# H_bridge.net
KiCad netlist of a schematic drawn in Altium Designer
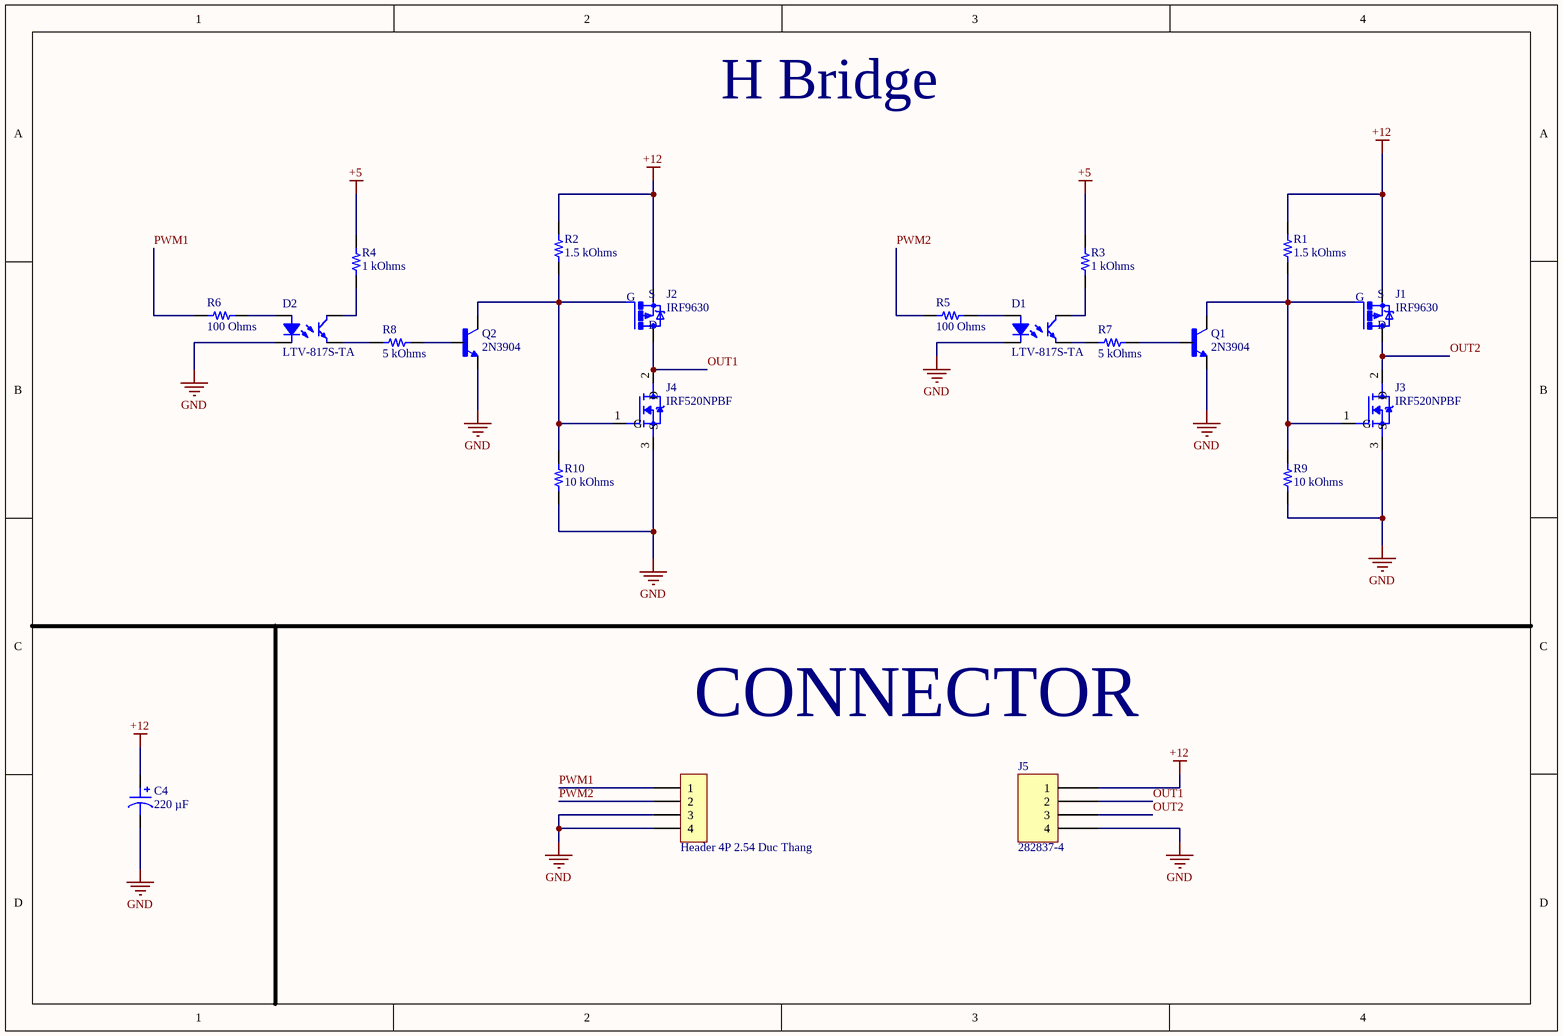
[diagram p0: H_bridge.SchDoc]

(export (version "E")
  (design (tool "Eeschema 10.0.6"))
  (components
    (comp (ref "C4")
      (value "220 µF")
      (footprint "CAP ALSMD POLY 8.3MM H10.0MM")
      (description "CAP ALUM POLY 220UF 20% 25V SMD")
      (fields (field (name "PART NUMBER") "PCR1E221MCL6GS") (field (name "MANUFACTURER") "Nichicon"))
      (libsource (lib "Celestial Altium Library - altium_library") (part "Polarised Capacitor"))
    )
    (comp (ref "D1")
      (value "LTV-817S-TA")
      (footprint "LITEON LTV-817")
      (description "OPTOISOLATR 5KV TRANSISTOR 4-SMD")
      (fields (field (name "MANUFACTURER") "Lite-On Inc."))
      (libsource (lib "Celestial Altium Library - altium_library") (part "Optoisolator"))
    )
    (comp (ref "D2")
      (value "LTV-817S-TA")
      (footprint "LITEON LTV-817")
      (description "OPTOISOLATR 5KV TRANSISTOR 4-SMD")
      (fields (field (name "MANUFACTURER") "Lite-On Inc."))
      (libsource (lib "Celestial Altium Library - altium_library") (part "Optoisolator"))
    )
    (comp (ref "H1")
      (value "Header 4P 2.54 Duc Thang")
      (footprint "XH2.54M-4")
      (description "Cắm")
      (libsource (lib "Header") (part "Header 4P 2.54 Duc Thang"))
    )
    (comp (ref "J1")
      (value "IRF9630")
      (footprint "TO220V")
      (fields (field (name "MF") "Vishay Siliconix"))
      (libsource (lib "IRF9630") (part "IRF9630"))
    )
    (comp (ref "J2")
      (value "IRF9630")
      (footprint "TO220V")
      (fields (field (name "MF") "Vishay Siliconix"))
      (libsource (lib "IRF9630") (part "IRF9630"))
    )
    (comp (ref "J3")
      (value "IRF520NPBF")
      (footprint "TO-220-3")
      (description "N-Channel 100V 9.7A _Tc_ 48W _Tc_ Through Hole TO-220AB")
      (fields (field (name "MF") "Infineon Technologies"))
      (libsource (lib "IRF520NPBF") (part "IRF520NPBF"))
    )
    (comp (ref "J4")
      (value "IRF520NPBF")
      (footprint "TO-220-3")
      (description "N-Channel 100V 9.7A _Tc_ 48W _Tc_ Through Hole TO-220AB")
      (fields (field (name "MF") "Infineon Technologies"))
      (libsource (lib "IRF520NPBF") (part "IRF520NPBF"))
    )
    (comp (ref "J5")
      (value "282837-4")
      (footprint "TE 282837-4")
      (description "TERM BLK 4P SIDE ENT 5.08MM PCB")
      (fields (field (name "MANUFACTURER") "TE Connectivity AMP Connectors") (field (name "VOLTAGE") "300 V"))
      (libsource (lib "Celestial Altium Library - altium_library") (part "4 Pin"))
    )
    (comp (ref "Q1")
      (value "2N3904")
      (footprint "TO92127P495H495-3")
      (description "TRANS NPN 40V 200MA TO92-3")
      (fields (field (name "MF") "Rectron"))
      (libsource (lib "2N3904") (part "2N3904"))
    )
    (comp (ref "Q2")
      (value "2N3904")
      (footprint "TO92127P495H495-3")
      (description "TRANS NPN 40V 200MA TO92-3")
      (fields (field (name "MF") "Rectron"))
      (libsource (lib "2N3904") (part "2N3904"))
    )
    (comp (ref "R1")
      (value "1.5 kOhms")
      (footprint "RES 0603_1608")
      (description "RES 1.5K OHM 0.1% 1/10W 0603")
      (fields (field (name "PART NUMBER") "RP0603BRD071K5L") (field (name "MANUFACTURER") "Yageo"))
      (libsource (lib "Celestial Altium Library - altium_library") (part "Resistor"))
    )
    (comp (ref "R2")
      (value "1.5 kOhms")
      (footprint "RES 0603_1608")
      (description "RES 1.5K OHM 0.1% 1/10W 0603")
      (fields (field (name "PART NUMBER") "RP0603BRD071K5L") (field (name "MANUFACTURER") "Yageo"))
      (libsource (lib "Celestial Altium Library - altium_library") (part "Resistor"))
    )
    (comp (ref "R3")
      (value "1 kOhms")
      (footprint "RES 0603_1608")
      (description "RES 1K OHM 0.1% 1/10W 0603")
      (fields (field (name "PART NUMBER") "RP0603BRD071KL") (field (name "MANUFACTURER") "Yageo"))
      (libsource (lib "Celestial Altium Library - altium_library") (part "Resistor"))
    )
    (comp (ref "R4")
      (value "1 kOhms")
      (footprint "RES 0603_1608")
      (description "RES 1K OHM 0.1% 1/10W 0603")
      (fields (field (name "PART NUMBER") "RP0603BRD071KL") (field (name "MANUFACTURER") "Yageo"))
      (libsource (lib "Celestial Altium Library - altium_library") (part "Resistor"))
    )
    (comp (ref "R5")
      (value "100 Ohms")
      (footprint "RES 0603_1608")
      (description "RES SMD 100 OHM 0.1% 1/10W 0603")
      (fields
        (field (name "PART NUMBER") "MCT06030D1000BP100")
        (field (name "MANUFACTURER") "Vishay Beyschlag")
      )
      (libsource (lib "Celestial Altium Library - altium_library") (part "Resistor"))
    )
    (comp (ref "R6")
      (value "100 Ohms")
      (footprint "RES 0603_1608")
      (description "RES SMD 100 OHM 0.1% 1/10W 0603")
      (fields
        (field (name "PART NUMBER") "MCT06030D1000BP100")
        (field (name "MANUFACTURER") "Vishay Beyschlag")
      )
      (libsource (lib "Celestial Altium Library - altium_library") (part "Resistor"))
    )
    (comp (ref "R7")
      (value "5 kOhms")
      (footprint "RES 0603_1608")
      (description "RES SMD 5K OHM 0.1% 0.15W 0603")
      (fields
        (field (name "PART NUMBER") "PNM0603E5001BST5")
        (field (name "MANUFACTURER") "Vishay Thin Film")
      )
      (libsource (lib "Celestial Altium Library - altium_library") (part "Resistor"))
    )
    (comp (ref "R8")
      (value "5 kOhms")
      (footprint "RES 0603_1608")
      (description "RES SMD 5K OHM 0.1% 0.15W 0603")
      (fields
        (field (name "PART NUMBER") "PNM0603E5001BST5")
        (field (name "MANUFACTURER") "Vishay Thin Film")
      )
      (libsource (lib "Celestial Altium Library - altium_library") (part "Resistor"))
    )
    (comp (ref "R9")
      (value "10 kOhms")
      (footprint "RES 0603_1608")
      (description "RES SMD 10K OHM 1/10W 0.1% 0603")
      (fields (field (name "PART NUMBER") "CRT0603-BY-1002EAS") (field (name "MANUFACTURER") "Bourns Inc."))
      (libsource (lib "Celestial Altium Library - altium_library") (part "Resistor"))
    )
    (comp (ref "R10")
      (value "10 kOhms")
      (footprint "RES 0603_1608")
      (description "RES SMD 10K OHM 1/10W 0.1% 0603")
      (fields (field (name "PART NUMBER") "CRT0603-BY-1002EAS") (field (name "MANUFACTURER") "Bourns Inc."))
      (libsource (lib "Celestial Altium Library - altium_library") (part "Resistor"))
    )
  )
  (nets
    (net (code "1") (name "+5") (class "Default")
      (node (ref "R3") (pin "2") (pinfunction "2_2") (pintype "passive"))
      (node (ref "R4") (pin "2") (pinfunction "2_2") (pintype "passive"))
    )
    (net (code "2") (name "+12") (class "Default")
      (node (ref "C4") (pin "1") (pinfunction "1_1") (pintype "passive"))
      (node (ref "J1") (pin "3") (pinfunction "S_3") (pintype "passive"))
      (node (ref "J2") (pin "3") (pinfunction "S_3") (pintype "passive"))
      (node (ref "J5") (pin "1") (pinfunction "1_1") (pintype "passive"))
      (node (ref "R1") (pin "2") (pinfunction "2_2") (pintype "passive"))
      (node (ref "R2") (pin "2") (pinfunction "2_2") (pintype "passive"))
    )
    (net (code "3") (name "/OUT1") (class "Default")
      (node (ref "J2") (pin "2") (pinfunction "D_2") (pintype "passive"))
      (node (ref "J4") (pin "2") (pinfunction "D_2") (pintype "passive"))
      (node (ref "J5") (pin "2") (pinfunction "2_2") (pintype "passive"))
    )
    (net (code "4") (name "/OUT2") (class "Default")
      (node (ref "J1") (pin "2") (pinfunction "D_2") (pintype "passive"))
      (node (ref "J3") (pin "2") (pinfunction "D_2") (pintype "passive"))
      (node (ref "J5") (pin "3") (pinfunction "3_3") (pintype "passive"))
    )
    (net (code "5") (name "/PWM1") (class "Default")
      (node (ref "H1") (pin "1") (pinfunction "1_1") (pintype "passive"))
      (node (ref "R6") (pin "1") (pinfunction "1_1") (pintype "passive"))
    )
    (net (code "6") (name "/PWM2") (class "Default")
      (node (ref "H1") (pin "2") (pinfunction "2_2") (pintype "passive"))
      (node (ref "R5") (pin "1") (pinfunction "1_1") (pintype "passive"))
    )
    (net (code "7") (name "GND") (class "Default")
      (node (ref "C4") (pin "2") (pinfunction "2_2") (pintype "passive"))
      (node (ref "D1") (pin "2") (pinfunction "2_2") (pintype "passive"))
      (node (ref "D2") (pin "2") (pinfunction "2_2") (pintype "passive"))
      (node (ref "H1") (pin "3") (pinfunction "3_3") (pintype "passive"))
      (node (ref "H1") (pin "4") (pinfunction "4_4") (pintype "passive"))
      (node (ref "J3") (pin "3") (pinfunction "S_3") (pintype "passive"))
      (node (ref "J4") (pin "3") (pinfunction "S_3") (pintype "passive"))
      (node (ref "J5") (pin "4") (pinfunction "4_4") (pintype "passive"))
      (node (ref "Q1") (pin "1") (pinfunction "E_1") (pintype "passive"))
      (node (ref "Q2") (pin "1") (pinfunction "E_1") (pintype "passive"))
      (node (ref "R10") (pin "1") (pinfunction "1_1") (pintype "passive"))
      (node (ref "R9") (pin "1") (pinfunction "1_1") (pintype "passive"))
    )
    (net (code "8") (name "Net-(D1-Pad1)") (class "Default")
      (node (ref "D1") (pin "1") (pinfunction "1_1") (pintype "passive"))
      (node (ref "R5") (pin "2") (pinfunction "2_2") (pintype "passive"))
    )
    (net (code "9") (name "Net-(D1-Pad3)") (class "Default")
      (node (ref "D1") (pin "3") (pinfunction "3_3") (pintype "passive"))
      (node (ref "R7") (pin "1") (pinfunction "1_1") (pintype "passive"))
    )
    (net (code "10") (name "Net-(D1-Pad4)") (class "Default")
      (node (ref "D1") (pin "4") (pinfunction "4_4") (pintype "passive"))
      (node (ref "R3") (pin "1") (pinfunction "1_1") (pintype "passive"))
    )
    (net (code "11") (name "Net-(D2-Pad1)") (class "Default")
      (node (ref "D2") (pin "1") (pinfunction "1_1") (pintype "passive"))
      (node (ref "R6") (pin "2") (pinfunction "2_2") (pintype "passive"))
    )
    (net (code "12") (name "Net-(D2-Pad3)") (class "Default")
      (node (ref "D2") (pin "3") (pinfunction "3_3") (pintype "passive"))
      (node (ref "R8") (pin "1") (pinfunction "1_1") (pintype "passive"))
    )
    (net (code "13") (name "Net-(D2-Pad4)") (class "Default")
      (node (ref "D2") (pin "4") (pinfunction "4_4") (pintype "passive"))
      (node (ref "R4") (pin "1") (pinfunction "1_1") (pintype "passive"))
    )
    (net (code "14") (name "Net-(J1-G)") (class "Default")
      (node (ref "J1") (pin "1") (pinfunction "G_1") (pintype "passive"))
      (node (ref "J3") (pin "1") (pinfunction "G_1") (pintype "passive"))
      (node (ref "Q1") (pin "3") (pinfunction "C_3") (pintype "passive"))
      (node (ref "R1") (pin "1") (pinfunction "1_1") (pintype "passive"))
      (node (ref "R9") (pin "2") (pinfunction "2_2") (pintype "passive"))
    )
    (net (code "15") (name "Net-(J2-G)") (class "Default")
      (node (ref "J2") (pin "1") (pinfunction "G_1") (pintype "passive"))
      (node (ref "J4") (pin "1") (pinfunction "G_1") (pintype "passive"))
      (node (ref "Q2") (pin "3") (pinfunction "C_3") (pintype "passive"))
      (node (ref "R10") (pin "2") (pinfunction "2_2") (pintype "passive"))
      (node (ref "R2") (pin "1") (pinfunction "1_1") (pintype "passive"))
    )
    (net (code "16") (name "Net-(Q1-B)") (class "Default")
      (node (ref "Q1") (pin "2") (pinfunction "B_2") (pintype "passive"))
      (node (ref "R7") (pin "2") (pinfunction "2_2") (pintype "passive"))
    )
    (net (code "17") (name "Net-(Q2-B)") (class "Default")
      (node (ref "Q2") (pin "2") (pinfunction "B_2") (pintype "passive"))
      (node (ref "R8") (pin "2") (pinfunction "2_2") (pintype "passive"))
    )
  )
)
